# Single_Mux_12.net
KiCad netlist of a schematic drawn in Altium Designer
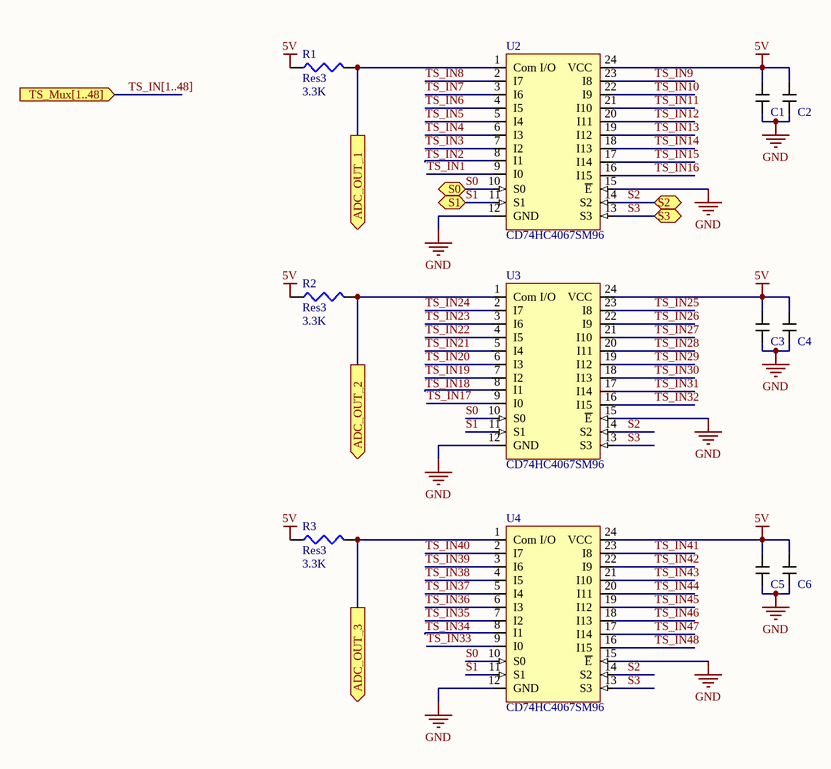
[diagram p0: Single_Mux_12.SchDoc]

(export (version "E")
  (design (tool "Eeschema 10.0.6"))
  (components
    (comp (ref "C1")
      (value "0.1uF Cap")
      (footprint "0.1uF_Kemet")
      (description "C0603C101K8GAC7867 Kemet Capacitor")
      (libsource (lib "0.1_uF_Kemet_Cap") (part "0.1uF Cap"))
    )
    (comp (ref "C2")
      (value "1uF Samsung Cap")
      (footprint "1uf_Samsung")
      (libsource (lib "1uF_Samsung_Cap") (part "1uF Samsung Cap"))
    )
    (comp (ref "C3")
      (value "0.1uF Cap")
      (footprint "0.1uF_Kemet")
      (description "C0603C101K8GAC7867 Kemet Capacitor")
      (libsource (lib "0.1_uF_Kemet_Cap") (part "0.1uF Cap"))
    )
    (comp (ref "C4")
      (value "1uF Samsung Cap")
      (footprint "1uf_Samsung")
      (libsource (lib "1uF_Samsung_Cap") (part "1uF Samsung Cap"))
    )
    (comp (ref "C5")
      (value "0.1uF Cap")
      (footprint "0.1uF_Kemet")
      (description "C0603C101K8GAC7867 Kemet Capacitor")
      (libsource (lib "0.1_uF_Kemet_Cap") (part "0.1uF Cap"))
    )
    (comp (ref "C6")
      (value "1uF Samsung Cap")
      (footprint "1uf_Samsung")
      (libsource (lib "1uF_Samsung_Cap") (part "1uF Samsung Cap"))
    )
    (comp (ref "R1")
      (value "Res3")
      (footprint "J1-0603")
      (description "Resistor")
      (fields (field (name "ALTIUM_VALUE") "3.3K") (field (name "PUBLISHER") "Altium Limited"))
      (libsource (lib "Miscellaneous Devices") (part "Res3"))
    )
    (comp (ref "R2")
      (value "Res3")
      (footprint "J1-0603")
      (description "Resistor")
      (fields (field (name "ALTIUM_VALUE") "3.3K") (field (name "PUBLISHER") "Altium Limited"))
      (libsource (lib "Miscellaneous Devices") (part "Res3"))
    )
    (comp (ref "R3")
      (value "Res3")
      (footprint "J1-0603")
      (description "Resistor")
      (fields (field (name "ALTIUM_VALUE") "3.3K") (field (name "PUBLISHER") "Altium Limited"))
      (libsource (lib "Miscellaneous Devices") (part "Res3"))
    )
    (comp (ref "U2")
      (value "CD74HC4067SM96")
      (footprint "SOIC-24_MUX")
      (libsource (lib "TI_Mux") (part "CD74HC4067SM96"))
    )
    (comp (ref "U3")
      (value "CD74HC4067SM96")
      (footprint "SOIC-24_MUX")
      (libsource (lib "TI_Mux") (part "CD74HC4067SM96"))
    )
    (comp (ref "U4")
      (value "CD74HC4067SM96")
      (footprint "SOIC-24_MUX")
      (libsource (lib "TI_Mux") (part "CD74HC4067SM96"))
    )
  )
  (nets
    (net (code "1") (name "/ADC_OUT_1") (class "Default")
      (node (ref "R1") (pin "2") (pinfunction "2_2") (pintype "passive"))
      (node (ref "U2") (pin "1") (pinfunction "Com_I/O_1") (pintype "bidirectional"))
    )
    (net (code "2") (name "/ADC_OUT_2") (class "Default")
      (node (ref "R2") (pin "2") (pinfunction "2_2") (pintype "passive"))
      (node (ref "U3") (pin "1") (pinfunction "Com_I/O_1") (pintype "bidirectional"))
    )
    (net (code "3") (name "/ADC_OUT_3") (class "Default")
      (node (ref "R3") (pin "2") (pinfunction "2_2") (pintype "passive"))
      (node (ref "U4") (pin "1") (pinfunction "Com_I/O_1") (pintype "bidirectional"))
    )
    (net (code "4") (name "/S0") (class "Default")
      (node (ref "U2") (pin "10") (pinfunction "S0_10") (pintype "input"))
      (node (ref "U3") (pin "10") (pinfunction "S0_10") (pintype "input"))
      (node (ref "U4") (pin "10") (pinfunction "S0_10") (pintype "input"))
    )
    (net (code "5") (name "/S1") (class "Default")
      (node (ref "U2") (pin "11") (pinfunction "S1_11") (pintype "input"))
      (node (ref "U3") (pin "11") (pinfunction "S1_11") (pintype "input"))
      (node (ref "U4") (pin "11") (pinfunction "S1_11") (pintype "input"))
    )
    (net (code "6") (name "/S2") (class "Default")
      (node (ref "U2") (pin "14") (pinfunction "S2_14") (pintype "input"))
      (node (ref "U3") (pin "14") (pinfunction "S2_14") (pintype "input"))
      (node (ref "U4") (pin "14") (pinfunction "S2_14") (pintype "input"))
    )
    (net (code "7") (name "/S3") (class "Default")
      (node (ref "U2") (pin "13") (pinfunction "S3_13") (pintype "input"))
      (node (ref "U3") (pin "13") (pinfunction "S3_13") (pintype "input"))
      (node (ref "U4") (pin "13") (pinfunction "S3_13") (pintype "input"))
    )
    (net (code "8") (name "/TS_IN1") (class "Default")
      (node (ref "U2") (pin "9") (pinfunction "I0_9") (pintype "passive"))
    )
    (net (code "9") (name "/TS_IN2") (class "Default")
      (node (ref "U2") (pin "8") (pinfunction "I1_8") (pintype "passive"))
    )
    (net (code "10") (name "/TS_IN3") (class "Default")
      (node (ref "U2") (pin "7") (pinfunction "I2_7") (pintype "passive"))
    )
    (net (code "11") (name "/TS_IN4") (class "Default")
      (node (ref "U2") (pin "6") (pinfunction "I3_6") (pintype "passive"))
    )
    (net (code "12") (name "/TS_IN5") (class "Default")
      (node (ref "U2") (pin "5") (pinfunction "I4_5") (pintype "passive"))
    )
    (net (code "13") (name "/TS_IN6") (class "Default")
      (node (ref "U2") (pin "4") (pinfunction "I5_4") (pintype "passive"))
    )
    (net (code "14") (name "/TS_IN7") (class "Default")
      (node (ref "U2") (pin "3") (pinfunction "I6_3") (pintype "passive"))
    )
    (net (code "15") (name "/TS_IN8") (class "Default")
      (node (ref "U2") (pin "2") (pinfunction "I7_2") (pintype "passive"))
    )
    (net (code "16") (name "/TS_IN9") (class "Default")
      (node (ref "U2") (pin "23") (pinfunction "I8_23") (pintype "passive"))
    )
    (net (code "17") (name "/TS_IN10") (class "Default")
      (node (ref "U2") (pin "22") (pinfunction "I9_22") (pintype "passive"))
    )
    (net (code "18") (name "/TS_IN11") (class "Default")
      (node (ref "U2") (pin "21") (pinfunction "I10_21") (pintype "passive"))
    )
    (net (code "19") (name "/TS_IN12") (class "Default")
      (node (ref "U2") (pin "20") (pinfunction "I11_20") (pintype "passive"))
    )
    (net (code "20") (name "/TS_IN13") (class "Default")
      (node (ref "U2") (pin "19") (pinfunction "I12_19") (pintype "passive"))
    )
    (net (code "21") (name "/TS_IN14") (class "Default")
      (node (ref "U2") (pin "18") (pinfunction "I13_18") (pintype "passive"))
    )
    (net (code "22") (name "/TS_IN15") (class "Default")
      (node (ref "U2") (pin "17") (pinfunction "I14_17") (pintype "passive"))
    )
    (net (code "23") (name "/TS_IN16") (class "Default")
      (node (ref "U2") (pin "16") (pinfunction "I15_16") (pintype "passive"))
    )
    (net (code "24") (name "/TS_IN17") (class "Default")
      (node (ref "U3") (pin "9") (pinfunction "I0_9") (pintype "passive"))
    )
    (net (code "25") (name "/TS_IN18") (class "Default")
      (node (ref "U3") (pin "8") (pinfunction "I1_8") (pintype "passive"))
    )
    (net (code "26") (name "/TS_IN19") (class "Default")
      (node (ref "U3") (pin "7") (pinfunction "I2_7") (pintype "passive"))
    )
    (net (code "27") (name "/TS_IN20") (class "Default")
      (node (ref "U3") (pin "6") (pinfunction "I3_6") (pintype "passive"))
    )
    (net (code "28") (name "/TS_IN21") (class "Default")
      (node (ref "U3") (pin "5") (pinfunction "I4_5") (pintype "passive"))
    )
    (net (code "29") (name "/TS_IN22") (class "Default")
      (node (ref "U3") (pin "4") (pinfunction "I5_4") (pintype "passive"))
    )
    (net (code "30") (name "/TS_IN23") (class "Default")
      (node (ref "U3") (pin "3") (pinfunction "I6_3") (pintype "passive"))
    )
    (net (code "31") (name "/TS_IN24") (class "Default")
      (node (ref "U3") (pin "2") (pinfunction "I7_2") (pintype "passive"))
    )
    (net (code "32") (name "/TS_IN25") (class "Default")
      (node (ref "U3") (pin "23") (pinfunction "I8_23") (pintype "passive"))
    )
    (net (code "33") (name "/TS_IN26") (class "Default")
      (node (ref "U3") (pin "22") (pinfunction "I9_22") (pintype "passive"))
    )
    (net (code "34") (name "/TS_IN27") (class "Default")
      (node (ref "U3") (pin "21") (pinfunction "I10_21") (pintype "passive"))
    )
    (net (code "35") (name "/TS_IN28") (class "Default")
      (node (ref "U3") (pin "20") (pinfunction "I11_20") (pintype "passive"))
    )
    (net (code "36") (name "/TS_IN29") (class "Default")
      (node (ref "U3") (pin "19") (pinfunction "I12_19") (pintype "passive"))
    )
    (net (code "37") (name "/TS_IN30") (class "Default")
      (node (ref "U3") (pin "18") (pinfunction "I13_18") (pintype "passive"))
    )
    (net (code "38") (name "/TS_IN31") (class "Default")
      (node (ref "U3") (pin "17") (pinfunction "I14_17") (pintype "passive"))
    )
    (net (code "39") (name "/TS_IN32") (class "Default")
      (node (ref "U3") (pin "16") (pinfunction "I15_16") (pintype "passive"))
    )
    (net (code "40") (name "/TS_IN33") (class "Default")
      (node (ref "U4") (pin "9") (pinfunction "I0_9") (pintype "passive"))
    )
    (net (code "41") (name "/TS_IN34") (class "Default")
      (node (ref "U4") (pin "8") (pinfunction "I1_8") (pintype "passive"))
    )
    (net (code "42") (name "/TS_IN35") (class "Default")
      (node (ref "U4") (pin "7") (pinfunction "I2_7") (pintype "passive"))
    )
    (net (code "43") (name "/TS_IN36") (class "Default")
      (node (ref "U4") (pin "6") (pinfunction "I3_6") (pintype "passive"))
    )
    (net (code "44") (name "/TS_IN37") (class "Default")
      (node (ref "U4") (pin "5") (pinfunction "I4_5") (pintype "passive"))
    )
    (net (code "45") (name "/TS_IN38") (class "Default")
      (node (ref "U4") (pin "4") (pinfunction "I5_4") (pintype "passive"))
    )
    (net (code "46") (name "/TS_IN39") (class "Default")
      (node (ref "U4") (pin "3") (pinfunction "I6_3") (pintype "passive"))
    )
    (net (code "47") (name "/TS_IN40") (class "Default")
      (node (ref "U4") (pin "2") (pinfunction "I7_2") (pintype "passive"))
    )
    (net (code "48") (name "/TS_IN41") (class "Default")
      (node (ref "U4") (pin "23") (pinfunction "I8_23") (pintype "passive"))
    )
    (net (code "49") (name "/TS_IN42") (class "Default")
      (node (ref "U4") (pin "22") (pinfunction "I9_22") (pintype "passive"))
    )
    (net (code "50") (name "/TS_IN43") (class "Default")
      (node (ref "U4") (pin "21") (pinfunction "I10_21") (pintype "passive"))
    )
    (net (code "51") (name "/TS_IN44") (class "Default")
      (node (ref "U4") (pin "20") (pinfunction "I11_20") (pintype "passive"))
    )
    (net (code "52") (name "/TS_IN45") (class "Default")
      (node (ref "U4") (pin "19") (pinfunction "I12_19") (pintype "passive"))
    )
    (net (code "53") (name "/TS_IN46") (class "Default")
      (node (ref "U4") (pin "18") (pinfunction "I13_18") (pintype "passive"))
    )
    (net (code "54") (name "/TS_IN47") (class "Default")
      (node (ref "U4") (pin "17") (pinfunction "I14_17") (pintype "passive"))
    )
    (net (code "55") (name "/TS_IN48") (class "Default")
      (node (ref "U4") (pin "16") (pinfunction "I15_16") (pintype "passive"))
    )
    (net (code "57") (name "5V") (class "Default")
      (node (ref "C1") (pin "2") (pinfunction "2_2") (pintype "passive"))
      (node (ref "C2") (pin "2") (pinfunction "2_2") (pintype "passive"))
      (node (ref "C3") (pin "2") (pinfunction "2_2") (pintype "passive"))
      (node (ref "C4") (pin "2") (pinfunction "2_2") (pintype "passive"))
      (node (ref "C5") (pin "2") (pinfunction "2_2") (pintype "passive"))
      (node (ref "C6") (pin "2") (pinfunction "2_2") (pintype "passive"))
      (node (ref "R1") (pin "1") (pinfunction "1_1") (pintype "passive"))
      (node (ref "R2") (pin "1") (pinfunction "1_1") (pintype "passive"))
      (node (ref "R3") (pin "1") (pinfunction "1_1") (pintype "passive"))
      (node (ref "U2") (pin "24") (pinfunction "VCC_24") (pintype "power_in"))
      (node (ref "U3") (pin "24") (pinfunction "VCC_24") (pintype "power_in"))
      (node (ref "U4") (pin "24") (pinfunction "VCC_24") (pintype "power_in"))
    )
    (net (code "58") (name "GND") (class "Default")
      (node (ref "C1") (pin "1") (pinfunction "1_1") (pintype "passive"))
      (node (ref "C2") (pin "1") (pinfunction "1_1") (pintype "passive"))
      (node (ref "C3") (pin "1") (pinfunction "1_1") (pintype "passive"))
      (node (ref "C4") (pin "1") (pinfunction "1_1") (pintype "passive"))
      (node (ref "C5") (pin "1") (pinfunction "1_1") (pintype "passive"))
      (node (ref "C6") (pin "1") (pinfunction "1_1") (pintype "passive"))
      (node (ref "U2") (pin "12") (pinfunction "GND_12") (pintype "power_in"))
      (node (ref "U2") (pin "15") (pinfunction "~{E}_15") (pintype "input"))
      (node (ref "U3") (pin "12") (pinfunction "GND_12") (pintype "power_in"))
      (node (ref "U3") (pin "15") (pinfunction "~{E}_15") (pintype "input"))
      (node (ref "U4") (pin "12") (pinfunction "GND_12") (pintype "power_in"))
      (node (ref "U4") (pin "15") (pinfunction "~{E}_15") (pintype "input"))
    )
  )
)
